# CAN2RPM-4layer.net
KiCad netlist of a schematic drawn in EasyEDA Pro
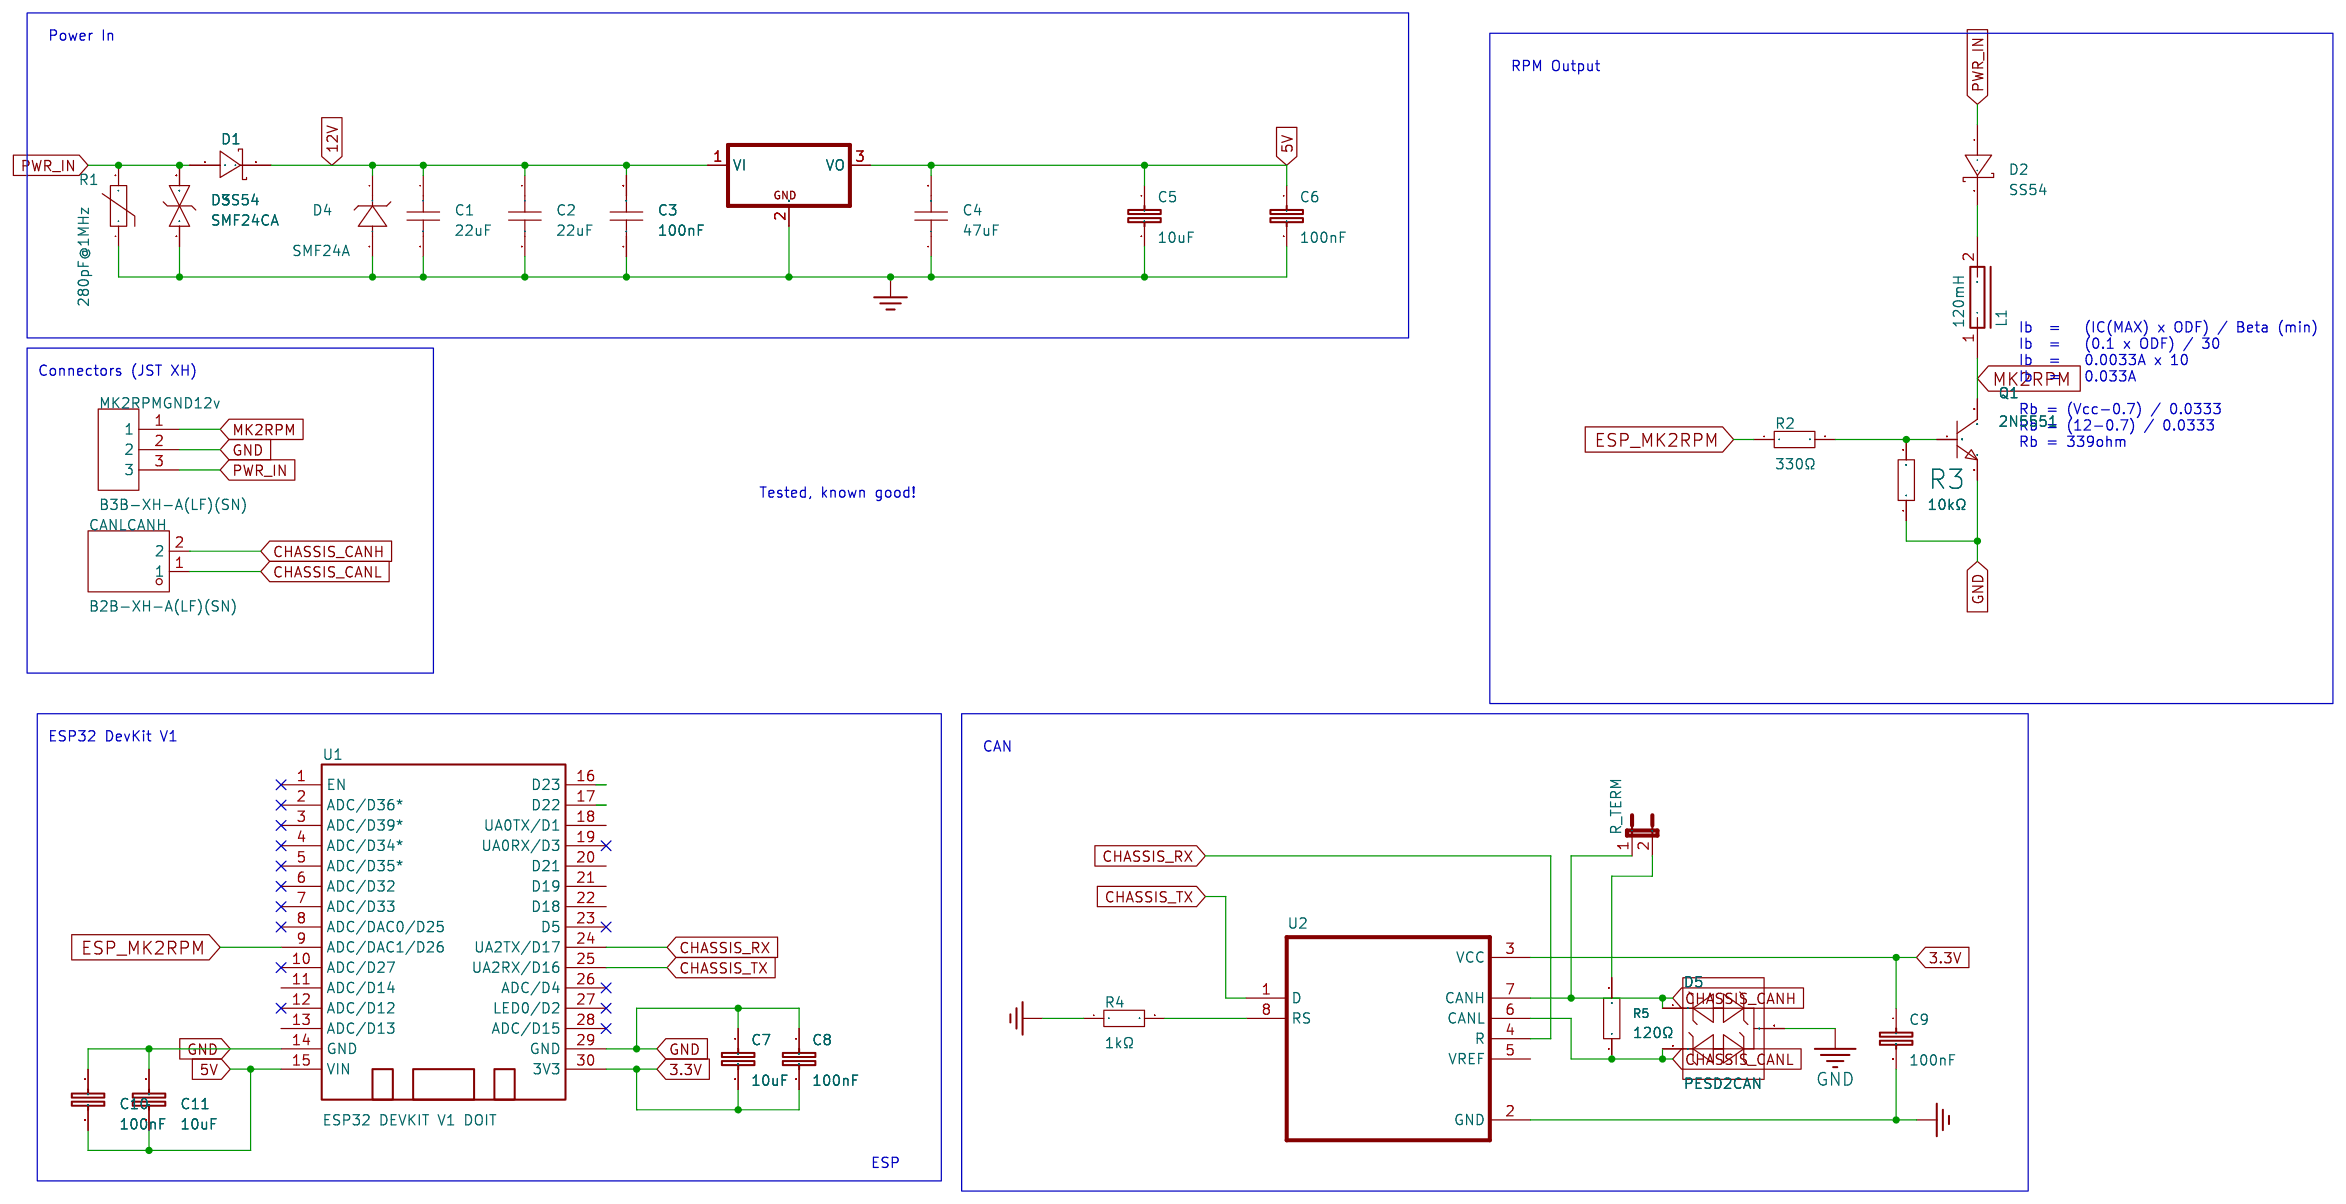
[diagram p0: schematic sheet]

(export (version "E")
  (design (tool "Eeschema 10.0.6"))
  (components
    (comp (ref "C1")
      (value "22uF")
      (footprint "easyedapro:C0805")
      (fields
        (field (name "Manufacturer Part") "HGC0805R5226M350NSLJ")
        (field (name "Manufacturer") "Chinocera(华瓷)")
      )
      (libsource (lib "easyedapro") (part "HGC0805R5226M350NSLJ"))
    )
    (comp (ref "C2")
      (value "22uF")
      (footprint "easyedapro:C0805")
      (fields
        (field (name "Manufacturer Part") "HGC0805R5226M350NSLJ")
        (field (name "Manufacturer") "Chinocera(华瓷)")
      )
      (libsource (lib "easyedapro") (part "HGC0805R5226M350NSLJ"))
    )
    (comp (ref "C3")
      (value "100nF")
      (description "Capacitance:100nF Tolerance:±10% Tolerance:±10% Voltage Rating:50V Temperature Coefficient:X7R")
      (fields
        (field (name "Manufacturer Part") "CL10B104KB8NNNC")
        (field (name "Manufacturer") "SAMSUNG(三星)")
      )
      (libsource (lib "easyedapro") (part "CSA0603X7R104K500JT"))
    )
    (comp (ref "C4")
      (value "47uF")
      (footprint "easyedapro:C0805")
      (description "Capacitance:47uF Tolerance:±20% Tolerance:±20% Voltage Rating:10V Temperature Coefficient:X5R")
      (fields
        (field (name "Manufacturer Part") "CL21A476MPYNNWE")
        (field (name "Manufacturer") "SAMSUNG(三星)")
      )
      (libsource (lib "easyedapro") (part "CL21A476MPYNNWE"))
    )
    (comp (ref "C5")
      (value "10uF")
      (fields
        (field (name "Manufacturer Part") "CL21A106KAYNNNE")
        (field (name "Manufacturer") "SAMSUNG(三星)")
      )
      (libsource (lib "easyedapro") (part "capacitor-wima_C_2.5/2"))
    )
    (comp (ref "C6")
      (value "100nF")
      (description "Capacitance:100nF Tolerance:±10% Tolerance:±10% Voltage Rating:50V Temperature Coefficient:-")
      (fields
        (field (name "Manufacturer Part") "CT41G-0805-2X1-50V-0.1μF-K(N)")
        (field (name "Manufacturer") "TORCH(火炬)")
      )
      (libsource (lib "easyedapro") (part "capacitor-wima_C_2.5/2"))
    )
    (comp (ref "C7")
      (value "10uF")
      (fields
        (field (name "Manufacturer Part") "CL21A106KAYNNNE")
        (field (name "Manufacturer") "SAMSUNG(三星)")
      )
      (libsource (lib "easyedapro") (part "capacitor-wima_C_2.5/2"))
    )
    (comp (ref "C8")
      (value "100nF")
      (description "Capacitance:100nF Tolerance:±10% Tolerance:±10% Voltage Rating:50V Temperature Coefficient:X7R")
      (fields
        (field (name "Manufacturer Part") "CC0603KRX7R9BB104")
        (field (name "Manufacturer") "YAGEO(国巨)")
      )
      (libsource (lib "easyedapro") (part "capacitor-wima_C_2.5/2"))
    )
    (comp (ref "C9")
      (value "100nF")
      (description "Capacitance:100nF Tolerance:±10% Tolerance:±10% Voltage Rating:50V Temperature Coefficient:-")
      (fields
        (field (name "Manufacturer Part") "CT41G-0805-2X1-50V-0.1μF-K(N)")
        (field (name "Manufacturer") "TORCH(火炬)")
      )
      (libsource (lib "easyedapro") (part "capacitor-wima_C_2.5/2"))
    )
    (comp (ref "C10")
      (value "100nF")
      (description "Capacitance:100nF Tolerance:±10% Tolerance:±10% Voltage Rating:50V Temperature Coefficient:X7R")
      (fields
        (field (name "Manufacturer Part") "CC0603KRX7R9BB104")
        (field (name "Manufacturer") "YAGEO(国巨)")
      )
      (libsource (lib "easyedapro") (part "capacitor-wima_C_2.5/2"))
    )
    (comp (ref "C11")
      (value "10uF")
      (fields
        (field (name "Manufacturer Part") "CL21A106KAYNNNE")
        (field (name "Manufacturer") "SAMSUNG(三星)")
      )
      (libsource (lib "easyedapro") (part "capacitor-wima_C_2.5/2"))
    )
    (comp (ref "CANLCANH")
      (value "B2B-XH-A(LF)(SN)")
      (footprint "easyedapro:CONN-TH_B2B-XH-A-LF-SN")
      (fields (field (name "Manufacturer") "JST"))
      (libsource (lib "easyedapro") (part "B2B-XH-A (LF)(SN)"))
    )
    (comp (ref "D1")
      (value "SS54")
      (footprint "easyedapro:SMA_L4.4-W2.8-LS5.4-R-RD")
      (fields (field (name "Manufacturer") "MDD(辰达半导体)"))
      (libsource (lib "easyedapro") (part "SS54_C22452"))
    )
    (comp (ref "D2")
      (value "SS54")
      (footprint "easyedapro:SMA_L4.4-W2.8-LS5.4-R-RD")
      (fields (field (name "Manufacturer") "MDD(辰达半导体)"))
      (libsource (lib "easyedapro") (part "SS54_C22452"))
    )
    (comp (ref "D3")
      (value "SMF24CA")
      (footprint "easyedapro:SOD-123FL_L2.8-W1.8-LS3.7-BI")
      (fields (field (name "Manufacturer") "晶导微电子"))
      (libsource (lib "easyedapro") (part "SMF24CA_C353294"))
    )
    (comp (ref "D4")
      (value "SMF24A")
      (footprint "easyedapro:SOD-123FL_L2.7-W1.8-LS3.8-RD")
      (fields (field (name "Manufacturer") "R+O(宏嘉诚)"))
      (libsource (lib "easyedapro") (part "SMF24A_C19077514"))
    )
    (comp (ref "D5")
      (value "PESD2CAN")
      (footprint "easyedapro:SOT-23-3_L2.9-W1.3-P1.90-LS2.4-BR")
      (fields (field (name "Manufacturer") "TECH PUBLIC(台舟)"))
      (libsource (lib "easyedapro") (part "PESD2CAN_C907830"))
    )
    (comp (ref "IC1")
      (value "L7805ABD2T-TR")
      (fields (field (name "Manufacturer") "ST(意法半导体)"))
      (libsource (lib "easyedapro") (part "linear_78*_TV"))
    )
    (comp (ref "L1")
      (value "120mH")
      (fields (field (name "Manufacturer Part") "DR125-124-R") (field (name "Manufacturer") "EATON(伊顿)"))
      (libsource (lib "easyedapro") (part "DR125_DR125_"))
    )
    (comp (ref "MK2RPMGND12v")
      (value "B3B-XH-A(LF)(SN)")
      (footprint "easyedapro:CONN-TH_3P-P2.50_A2501WV2-3P")
      (fields (field (name "Manufacturer") "JST"))
      (libsource (lib "easyedapro") (part "B3B-XH-A(LF)(SN)"))
    )
    (comp (ref "Q1")
      (value "2N5551")
      (footprint "easyedapro:SOT-23-3_L2.9-W1.4-P1.90-LS2.5-BR")
      (fields (field (name "Manufacturer") "RUILON(瑞隆源)"))
      (libsource (lib "easyedapro") (part "2N5551_C7529570"))
    )
    (comp (ref "R1")
      (value "280pF@1MHz")
      (footprint "easyedapro:R0805")
      (fields (field (name "Manufacturer Part") "FPV201209E260PKT") (field (name "Manufacturer") "FH(风华)"))
      (libsource (lib "easyedapro") (part "FPV201209E260PKT"))
    )
    (comp (ref "R2")
      (value "330Ω")
      (footprint "easyedapro:R0603")
      (fields
        (field (name "Manufacturer Part") "0603WAF3300T5E")
        (field (name "Manufacturer") "UNI-ROYAL(厚声)")
      )
      (libsource (lib "easyedapro") (part "0603WAF3300T5E"))
    )
    (comp (ref "R3")
      (value "10kΩ")
      (footprint "easyedapro:R0603")
      (fields
        (field (name "Manufacturer Part") "0603WAF1002T5E")
        (field (name "Manufacturer") "UNI-ROYAL(厚声)")
      )
      (libsource (lib "easyedapro") (part "0603WAF1002T5E"))
    )
    (comp (ref "R4")
      (value "1kΩ")
      (footprint "easyedapro:R0603")
      (fields
        (field (name "Manufacturer Part") "0603WAF1001T5E")
        (field (name "Manufacturer") "UNI-ROYAL(厚声)")
      )
      (libsource (lib "easyedapro") (part "0603WAF1001T5E"))
    )
    (comp (ref "R5")
      (value "120Ω")
      (footprint "easyedapro:R0603")
      (fields
        (field (name "Manufacturer Part") "0603WAF1200T5E")
        (field (name "Manufacturer") "UNI-ROYAL(厚声)")
      )
      (libsource (lib "easyedapro") (part "0603WAF1200T5E"))
    )
    (comp (ref "R_TERM")
      (value "PZ254V-11-02P")
      (fields (field (name "Manufacturer") "XFCN(兴飞)"))
      (libsource (lib "easyedapro") (part "jumper_JP1E_"))
    )
    (comp (ref "U1")
      (value "ESP32 DEVKIT V1 DOIT")
      (footprint "easyedapro:DOIT-ESP32-DEVKIT-V1")
      (libsource (lib "easyedapro") (part "ESP32 DEVKIT V1 DOIT"))
    )
    (comp (ref "U2")
      (value "SN65HVD230DR")
      (fields (field (name "Manufacturer") "TI(德州仪器)"))
      (libsource (lib "easyedapro") (part "SN65HVD230DR_SN65HVD230DR_"))
    )
  )
  (nets
    (net (code "1") (name "3.3V") (class "Default")
      (node (ref "C7") (pin "2") (pinfunction "2_2") (pintype "unspecified"))
      (node (ref "C8") (pin "2") (pinfunction "2_2") (pintype "unspecified"))
      (node (ref "C9") (pin "1") (pinfunction "1_1") (pintype "unspecified"))
      (node (ref "U1") (pin "30") (pinfunction "3V3_30") (pintype "bidirectional"))
      (node (ref "U2") (pin "3") (pinfunction "VCC_3") (pintype "unspecified"))
    )
    (net (code "2") (name "5V") (class "Default")
      (node (ref "C10") (pin "1") (pinfunction "1_1") (pintype "unspecified"))
      (node (ref "C11") (pin "1") (pinfunction "1_1") (pintype "unspecified"))
      (node (ref "C4") (pin "2") (pinfunction "2_2") (pintype "unspecified"))
      (node (ref "C5") (pin "1") (pinfunction "1_1") (pintype "unspecified"))
      (node (ref "C6") (pin "1") (pinfunction "1_1") (pintype "unspecified"))
      (node (ref "IC1") (pin "3") (pinfunction "VO_3") (pintype "unspecified"))
      (node (ref "U1") (pin "15") (pinfunction "VIN_15") (pintype "input"))
    )
    (net (code "3") (name "12V") (class "Default")
      (node (ref "C1") (pin "1") (pinfunction "1_1") (pintype "unspecified"))
      (node (ref "C2") (pin "1") (pinfunction "1_1") (pintype "unspecified"))
      (node (ref "C3") (pin "2") (pinfunction "2_2") (pintype "unspecified"))
      (node (ref "D1") (pin "2") (pinfunction "K_2") (pintype "unspecified"))
      (node (ref "D4") (pin "1") (pinfunction "K_1") (pintype "unspecified"))
      (node (ref "IC1") (pin "1") (pinfunction "VI_1") (pintype "input"))
    )
    (net (code "4") (name "CHASSIS_CANH") (class "Default")
      (node (ref "CANLCANH") (pin "2") (pinfunction "2_2") (pintype "unspecified"))
      (node (ref "D5") (pin "1") (pinfunction "1_1") (pintype "unspecified"))
      (node (ref "R_TERM") (pin "1") (pinfunction "1_1") (pintype "unspecified"))
      (node (ref "U2") (pin "7") (pinfunction "CANH_7") (pintype "output"))
    )
    (net (code "5") (name "CHASSIS_CANL") (class "Default")
      (node (ref "CANLCANH") (pin "1") (pinfunction "1_1") (pintype "unspecified"))
      (node (ref "D5") (pin "2") (pinfunction "2_2") (pintype "unspecified"))
      (node (ref "R5") (pin "1") (pinfunction "1_1") (pintype "input"))
      (node (ref "U2") (pin "6") (pinfunction "CANL_6") (pintype "output"))
    )
    (net (code "6") (name "CHASSIS_RX") (class "Default")
      (node (ref "U1") (pin "24") (pinfunction "UA2TX/D17_24") (pintype "bidirectional"))
      (node (ref "U2") (pin "4") (pinfunction "R_4") (pintype "output"))
    )
    (net (code "7") (name "CHASSIS_TX") (class "Default")
      (node (ref "U1") (pin "25") (pinfunction "UA2RX/D16_25") (pintype "bidirectional"))
      (node (ref "U2") (pin "1") (pinfunction "D_1") (pintype "input"))
    )
    (net (code "8") (name "ESP_MK2RPM") (class "Default")
      (node (ref "R2") (pin "1") (pinfunction "1_1") (pintype "input"))
      (node (ref "U1") (pin "9") (pinfunction "ADC/DAC1/D26_9") (pintype "bidirectional"))
    )
    (net (code "9") (name "GND") (class "Default")
      (node (ref "C1") (pin "2") (pinfunction "2_2") (pintype "unspecified"))
      (node (ref "C10") (pin "2") (pinfunction "2_2") (pintype "unspecified"))
      (node (ref "C11") (pin "2") (pinfunction "2_2") (pintype "unspecified"))
      (node (ref "C2") (pin "2") (pinfunction "2_2") (pintype "unspecified"))
      (node (ref "C3") (pin "1") (pinfunction "1_1") (pintype "unspecified"))
      (node (ref "C4") (pin "1") (pinfunction "1_1") (pintype "unspecified"))
      (node (ref "C5") (pin "2") (pinfunction "2_2") (pintype "unspecified"))
      (node (ref "C6") (pin "2") (pinfunction "2_2") (pintype "unspecified"))
      (node (ref "C7") (pin "1") (pinfunction "1_1") (pintype "unspecified"))
      (node (ref "C8") (pin "1") (pinfunction "1_1") (pintype "unspecified"))
      (node (ref "C9") (pin "2") (pinfunction "2_2") (pintype "unspecified"))
      (node (ref "D3") (pin "1") (pinfunction "1_1") (pintype "input"))
      (node (ref "D4") (pin "2") (pinfunction "A_2") (pintype "unspecified"))
      (node (ref "D5") (pin "3") (pinfunction "3_3") (pintype "unspecified"))
      (node (ref "IC1") (pin "2") (pinfunction "GND_2") (pintype "unspecified"))
      (node (ref "MK2RPMGND12v") (pin "2") (pinfunction "2_2") (pintype "unspecified"))
      (node (ref "Q1") (pin "2") (pinfunction "E_2") (pintype "unspecified"))
      (node (ref "R1") (pin "1") (pinfunction "1_1") (pintype "unspecified"))
      (node (ref "R3") (pin "1") (pinfunction "1_1") (pintype "input"))
      (node (ref "R4") (pin "1") (pinfunction "1_1") (pintype "input"))
      (node (ref "U1") (pin "14") (pinfunction "GND_14") (pintype "bidirectional"))
      (node (ref "U1") (pin "29") (pinfunction "GND_29") (pintype "bidirectional"))
      (node (ref "U2") (pin "2") (pinfunction "GND_2") (pintype "unspecified"))
    )
    (net (code "10") (name "MK2RPM") (class "Default")
      (node (ref "L1") (pin "1") (pinfunction "1_1") (pintype "unspecified"))
      (node (ref "MK2RPMGND12v") (pin "1") (pinfunction "1_1") (pintype "unspecified"))
      (node (ref "Q1") (pin "3") (pinfunction "C_3") (pintype "unspecified"))
    )
    (net (code "11") (name "Net-(D2-K)") (class "Default")
      (node (ref "D2") (pin "2") (pinfunction "K_2") (pintype "unspecified"))
      (node (ref "L1") (pin "2") (pinfunction "2_2") (pintype "unspecified"))
    )
    (net (code "12") (name "Net-(Q1-B)") (class "Default")
      (node (ref "Q1") (pin "1") (pinfunction "B_1") (pintype "unspecified"))
      (node (ref "R2") (pin "2") (pinfunction "2_2") (pintype "input"))
      (node (ref "R3") (pin "2") (pinfunction "2_2") (pintype "input"))
    )
    (net (code "13") (name "Net-(R5-Pad2)") (class "Default")
      (node (ref "R5") (pin "2") (pinfunction "2_2") (pintype "input"))
      (node (ref "R_TERM") (pin "2") (pinfunction "2_2") (pintype "unspecified"))
    )
    (net (code "14") (name "Net-(U2-RS)") (class "Default")
      (node (ref "R4") (pin "2") (pinfunction "2_2") (pintype "input"))
      (node (ref "U2") (pin "8") (pinfunction "RS_8") (pintype "input"))
    )
    (net (code "15") (name "PWR_IN") (class "Default")
      (node (ref "D1") (pin "1") (pinfunction "A_1") (pintype "unspecified"))
      (node (ref "D2") (pin "1") (pinfunction "A_1") (pintype "unspecified"))
      (node (ref "D3") (pin "2") (pinfunction "2_2") (pintype "input"))
      (node (ref "MK2RPMGND12v") (pin "3") (pinfunction "3_3") (pintype "unspecified"))
      (node (ref "R1") (pin "2") (pinfunction "2_2") (pintype "unspecified"))
    )
    (net (code "16") (name "unconnected-(U1-ADC{slash}D4-Pad26)") (class "Default")
      (node (ref "U1") (pin "26") (pinfunction "ADC/D4_26") (pintype "bidirectional+no_connect"))
    )
    (net (code "17") (name "unconnected-(U1-ADC{slash}D12-Pad12)") (class "Default")
      (node (ref "U1") (pin "12") (pinfunction "ADC/D12_12") (pintype "bidirectional+no_connect"))
    )
    (net (code "18") (name "unconnected-(U1-ADC{slash}D13-Pad13)") (class "Default")
      (node (ref "U1") (pin "13") (pinfunction "ADC/D13_13") (pintype "bidirectional"))
    )
    (net (code "19") (name "unconnected-(U1-ADC{slash}D14-Pad11)") (class "Default")
      (node (ref "U1") (pin "11") (pinfunction "ADC/D14_11") (pintype "bidirectional"))
    )
    (net (code "20") (name "unconnected-(U1-ADC{slash}D15-Pad28)") (class "Default")
      (node (ref "U1") (pin "28") (pinfunction "ADC/D15_28") (pintype "bidirectional+no_connect"))
    )
    (net (code "21") (name "unconnected-(U1-ADC{slash}D27-Pad10)") (class "Default")
      (node (ref "U1") (pin "10") (pinfunction "ADC/D27_10") (pintype "bidirectional+no_connect"))
    )
    (net (code "22") (name "unconnected-(U1-ADC{slash}D32-Pad6)") (class "Default")
      (node (ref "U1") (pin "6") (pinfunction "ADC/D32_6") (pintype "bidirectional+no_connect"))
    )
    (net (code "23") (name "unconnected-(U1-ADC{slash}D33-Pad7)") (class "Default")
      (node (ref "U1") (pin "7") (pinfunction "ADC/D33_7") (pintype "bidirectional+no_connect"))
    )
    (net (code "24") (name "unconnected-(U1-ADC{slash}D34*-Pad4)") (class "Default")
      (node (ref "U1") (pin "4") (pinfunction "ADC/D34*_4") (pintype "input+no_connect"))
    )
    (net (code "25") (name "unconnected-(U1-ADC{slash}D35*-Pad5)") (class "Default")
      (node (ref "U1") (pin "5") (pinfunction "ADC/D35*_5") (pintype "input+no_connect"))
    )
    (net (code "26") (name "unconnected-(U1-ADC{slash}D36*-Pad2)") (class "Default")
      (node (ref "U1") (pin "2") (pinfunction "ADC/D36*_2") (pintype "input+no_connect"))
    )
    (net (code "27") (name "unconnected-(U1-ADC{slash}D39*-Pad3)") (class "Default")
      (node (ref "U1") (pin "3") (pinfunction "ADC/D39*_3") (pintype "input+no_connect"))
    )
    (net (code "28") (name "unconnected-(U1-ADC{slash}DAC0{slash}D25-Pad8)") (class "Default")
      (node (ref "U1") (pin "8") (pinfunction "ADC/DAC0/D25_8") (pintype "bidirectional+no_connect"))
    )
    (net (code "29") (name "unconnected-(U1-D5-Pad23)") (class "Default")
      (node (ref "U1") (pin "23") (pinfunction "D5_23") (pintype "bidirectional+no_connect"))
    )
    (net (code "30") (name "unconnected-(U1-D18-Pad22)") (class "Default")
      (node (ref "U1") (pin "22") (pinfunction "D18_22") (pintype "bidirectional"))
    )
    (net (code "31") (name "unconnected-(U1-D19-Pad21)") (class "Default")
      (node (ref "U1") (pin "21") (pinfunction "D19_21") (pintype "bidirectional"))
    )
    (net (code "32") (name "unconnected-(U1-D21-Pad20)") (class "Default")
      (node (ref "U1") (pin "20") (pinfunction "D21_20") (pintype "bidirectional"))
    )
    (net (code "33") (name "unconnected-(U1-D22-Pad17)") (class "Default")
      (node (ref "U1") (pin "17") (pinfunction "D22_17") (pintype "bidirectional"))
    )
    (net (code "34") (name "unconnected-(U1-D23-Pad16)") (class "Default")
      (node (ref "U1") (pin "16") (pinfunction "D23_16") (pintype "bidirectional"))
    )
    (net (code "35") (name "unconnected-(U1-EN-Pad1)") (class "Default")
      (node (ref "U1") (pin "1") (pinfunction "EN_1") (pintype "bidirectional+no_connect"))
    )
    (net (code "36") (name "unconnected-(U1-LED0{slash}D2-Pad27)") (class "Default")
      (node (ref "U1") (pin "27") (pinfunction "LED0/D2_27") (pintype "bidirectional+no_connect"))
    )
    (net (code "37") (name "unconnected-(U1-UA0RX{slash}D3-Pad19)") (class "Default")
      (node (ref "U1") (pin "19") (pinfunction "UA0RX/D3_19") (pintype "bidirectional+no_connect"))
    )
    (net (code "38") (name "unconnected-(U1-UA0TX{slash}D1-Pad18)") (class "Default")
      (node (ref "U1") (pin "18") (pinfunction "UA0TX/D1_18") (pintype "bidirectional"))
    )
    (net (code "39") (name "unconnected-(U2-VREF-Pad5)") (class "Default")
      (node (ref "U2") (pin "5") (pinfunction "VREF_5") (pintype "output"))
    )
  )
)
